# SCH_IR.net
KiCad netlist of a schematic drawn in Altium Designer
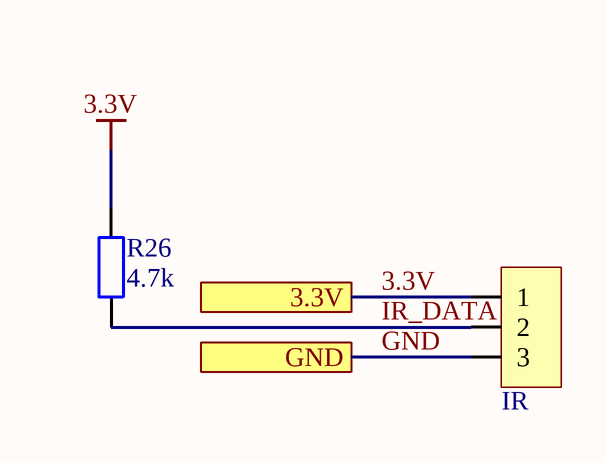
[diagram p0: SCH_IR.SchDoc]

(export (version "E")
  (design (tool "Eeschema 10.0.6"))
  (components
    (comp (ref "JP2")
      (value "IR")
      (footprint "JP 1x3 CT")
      (description "Cắm")
      (libsource (lib "Altium_Lib_by_KhueNguyenCreator") (part "JP 1x3 2.54 Cai Thang"))
    )
    (comp (ref "R26")
      (value "4.7k")
      (footprint "tro smd 0805")
      (description "Dán")
      (libsource (lib "Altium_Lib_by_KhueNguyenCreator") (part "Tro 0805 5% 4.7k"))
    )
  )
  (nets
    (net (code "1") (name "/GND") (class "Default")
      (node (ref "JP2") (pin "3") (pinfunction "3_3") (pintype "passive"))
    )
    (net (code "2") (name "/IR_DATA") (class "Default")
      (node (ref "JP2") (pin "2") (pinfunction "2_2") (pintype "passive"))
      (node (ref "R26") (pin "1") (pinfunction "1_1") (pintype "passive"))
    )
    (net (code "3") (name "3.3V") (class "Default")
      (node (ref "JP2") (pin "1") (pinfunction "1_1") (pintype "passive"))
      (node (ref "R26") (pin "2") (pinfunction "2_2") (pintype "passive"))
    )
  )
)
